# CAN.net
KiCad netlist of a schematic drawn in EAGLE
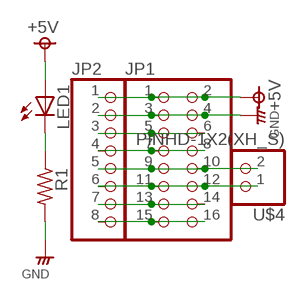
[diagram p0: schematic, sheet 1]

(export (version "E")
  (design (tool "Eeschema 10.0.6"))
  (components
    (comp (ref "JP1")
      (value "PINHD-2X8")
      (footprint "eagle-import:2X08")
      (libsource (lib "eagle-import") (part "PINHD-2X8"))
    )
    (comp (ref "JP2")
      (value "PINHD-1X8")
      (footprint "eagle-import:1X08")
      (libsource (lib "eagle-import") (part "PINHD-1X8"))
    )
    (comp (ref "LED1")
      (value "LED3MM")
      (footprint "eagle-import:LED3MM")
      (libsource (lib "eagle-import") (part "LED3MM"))
    )
    (comp (ref "R1")
      (value "RESISTORS-3")
      (footprint "eagle-import:R_0.3")
      (libsource (lib "eagle-import") (part "RESISTORS-3"))
    )
    (comp (ref "U$4")
      (value "PINHD-1X2(XH_S)")
      (footprint "eagle-import:1X2(XH-S)")
      (libsource (lib "eagle-import") (part "PINHD-1X2(XH_S)"))
    )
  )
  (nets
    (net (code "1") (name "/+5V") (class "Default")
      (node (ref "JP1") (pin "1") (pinfunction "1_1") (pintype "passive"))
      (node (ref "JP1") (pin "2") (pinfunction "2_2") (pintype "passive"))
      (node (ref "JP2") (pin "1") (pinfunction "1_1") (pintype "passive"))
      (node (ref "LED1") (pin "A") (pinfunction "A_A") (pintype "passive"))
    )
    (net (code "2") (name "GND") (class "Default")
      (node (ref "JP1") (pin "3") (pinfunction "3_3") (pintype "passive"))
      (node (ref "JP1") (pin "4") (pinfunction "4_4") (pintype "passive"))
      (node (ref "JP2") (pin "2") (pinfunction "2_2") (pintype "passive"))
      (node (ref "R1") (pin "2") (pinfunction "2_2") (pintype "passive"))
    )
    (net (code "3") (name "Net-(JP1-Pad5)") (class "Default")
      (node (ref "JP1") (pin "5") (pinfunction "5_5") (pintype "passive"))
      (node (ref "JP1") (pin "6") (pinfunction "6_6") (pintype "passive"))
      (node (ref "JP2") (pin "3") (pinfunction "3_3") (pintype "passive"))
    )
    (net (code "4") (name "Net-(JP1-Pad7)") (class "Default")
      (node (ref "JP1") (pin "7") (pinfunction "7_7") (pintype "passive"))
      (node (ref "JP1") (pin "8") (pinfunction "8_8") (pintype "passive"))
      (node (ref "JP2") (pin "4") (pinfunction "4_4") (pintype "passive"))
    )
    (net (code "5") (name "Net-(JP1-Pad10)") (class "Default")
      (node (ref "JP1") (pin "10") (pinfunction "10_10") (pintype "passive"))
      (node (ref "JP1") (pin "9") (pinfunction "9_9") (pintype "passive"))
      (node (ref "JP2") (pin "5") (pinfunction "5_5") (pintype "passive"))
      (node (ref "U$4") (pin "2") (pinfunction "2_2") (pintype "passive"))
    )
    (net (code "6") (name "Net-(JP1-Pad11)") (class "Default")
      (node (ref "JP1") (pin "11") (pinfunction "11_11") (pintype "passive"))
      (node (ref "JP1") (pin "12") (pinfunction "12_12") (pintype "passive"))
      (node (ref "JP2") (pin "6") (pinfunction "6_6") (pintype "passive"))
      (node (ref "U$4") (pin "1") (pinfunction "1_1") (pintype "passive"))
    )
    (net (code "7") (name "Net-(JP1-Pad13)") (class "Default")
      (node (ref "JP1") (pin "13") (pinfunction "13_13") (pintype "passive"))
      (node (ref "JP1") (pin "14") (pinfunction "14_14") (pintype "passive"))
      (node (ref "JP2") (pin "7") (pinfunction "7_7") (pintype "passive"))
    )
    (net (code "8") (name "Net-(JP1-Pad15)") (class "Default")
      (node (ref "JP1") (pin "15") (pinfunction "15_15") (pintype "passive"))
      (node (ref "JP1") (pin "16") (pinfunction "16_16") (pintype "passive"))
      (node (ref "JP2") (pin "8") (pinfunction "8_8") (pintype "passive"))
    )
    (net (code "9") (name "Net-(LED1-C)") (class "Default")
      (node (ref "LED1") (pin "K") (pinfunction "C_K") (pintype "passive"))
      (node (ref "R1") (pin "1") (pinfunction "1_1") (pintype "passive"))
    )
  )
)
